# 485.net
KiCad netlist of a schematic drawn in Altium Designer
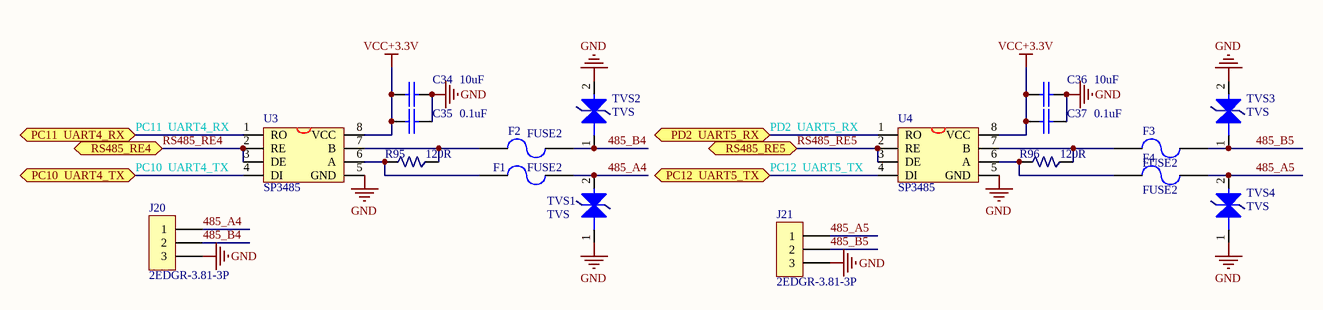
[diagram p0: 485.SchDoc]

(export (version "E")
  (design (tool "Eeschema 10.0.6"))
  (components
    (comp (ref "C34") (value "10uF") (footprint "0805") (libsource (lib "INSPUR_SCH") (part "CAP")))
    (comp (ref "C35") (value "0.1uF") (footprint "0603") (libsource (lib "INSPUR_SCH") (part "CAP")))
    (comp (ref "C36") (value "10uF") (footprint "0805") (libsource (lib "INSPUR_SCH") (part "CAP")))
    (comp (ref "C37") (value "0.1uF") (footprint "0603") (libsource (lib "INSPUR_SCH") (part "CAP")))
    (comp (ref "F1")
      (value "FUSE2")
      (footprint "0805")
      (description "SMD0805P010TS")
      (libsource (lib "INSPUR_SCH") (part "FUSE2"))
    )
    (comp (ref "F2")
      (value "FUSE2")
      (footprint "0805")
      (description "SMD0805P010TS")
      (libsource (lib "INSPUR_SCH") (part "FUSE2"))
    )
    (comp (ref "F3")
      (value "FUSE2")
      (footprint "0805")
      (description "SMD0805P010TS")
      (libsource (lib "INSPUR_SCH") (part "FUSE2"))
    )
    (comp (ref "F4")
      (value "FUSE2")
      (footprint "0805")
      (description "SMD0805P010TS")
      (libsource (lib "INSPUR_SCH") (part "FUSE2"))
    )
    (comp (ref "J20")
      (value "2EDGR-3.81-3P")
      (footprint "3.81-3P")
      (libsource (lib "INSPUR_PCB") (part "SIP3A-2.50（带槽）"))
    )
    (comp (ref "J21")
      (value "2EDGR-3.81-3P")
      (footprint "3.81-3P")
      (libsource (lib "INSPUR_PCB") (part "SIP3A-2.50（带槽）"))
    )
    (comp (ref "R95")
      (value "120R")
      (footprint "0603")
      (description "高精度电阻")
      (libsource (lib "8CF_V6") (part "RES-1%"))
    )
    (comp (ref "R96")
      (value "120R")
      (footprint "0603")
      (description "高精度电阻")
      (libsource (lib "8CF_V6") (part "RES-1%"))
    )
    (comp (ref "TVS1")
      (value "TVS")
      (footprint "SMB")
      (description "SMBJ12CA")
      (libsource (lib "INSPUR_SCH") (part "TVS"))
    )
    (comp (ref "TVS2")
      (value "TVS")
      (footprint "SMB")
      (description "SMBJ12CA")
      (libsource (lib "INSPUR_SCH") (part "TVS"))
    )
    (comp (ref "TVS3")
      (value "TVS")
      (footprint "SMB")
      (description "SMBJ12CA")
      (libsource (lib "INSPUR_SCH") (part "TVS"))
    )
    (comp (ref "TVS4")
      (value "TVS")
      (footprint "SMB")
      (description "SMBJ12CA")
      (libsource (lib "INSPUR_SCH") (part "TVS"))
    )
    (comp (ref "U3") (value "SP3485") (footprint "SOP-8") (libsource (lib "mylib") (part "MAX3485")))
    (comp (ref "U4") (value "SP3485") (footprint "SOP-8") (libsource (lib "mylib") (part "MAX3485")))
  )
  (nets
    (net (code "1") (name "/485_A4") (class "Default")
      (node (ref "F1") (pin "2") (pinfunction "2_2") (pintype "passive"))
      (node (ref "J20") (pin "1") (pinfunction "1_1") (pintype "passive"))
      (node (ref "TVS1") (pin "2") (pinfunction "K_2") (pintype "passive"))
    )
    (net (code "2") (name "/485_A5") (class "Default")
      (node (ref "F4") (pin "2") (pinfunction "2_2") (pintype "passive"))
      (node (ref "J21") (pin "1") (pinfunction "1_1") (pintype "passive"))
      (node (ref "TVS4") (pin "2") (pinfunction "K_2") (pintype "passive"))
    )
    (net (code "3") (name "/485_B4") (class "Default")
      (node (ref "F2") (pin "2") (pinfunction "2_2") (pintype "passive"))
      (node (ref "J20") (pin "2") (pinfunction "2_2") (pintype "passive"))
      (node (ref "TVS2") (pin "1") (pinfunction "A_1") (pintype "passive"))
    )
    (net (code "4") (name "/485_B5") (class "Default")
      (node (ref "F3") (pin "2") (pinfunction "2_2") (pintype "passive"))
      (node (ref "J21") (pin "2") (pinfunction "2_2") (pintype "passive"))
      (node (ref "TVS3") (pin "1") (pinfunction "A_1") (pintype "passive"))
    )
    (net (code "5") (name "/PC10  UART4_TX") (class "Default")
      (node (ref "U3") (pin "4") (pinfunction "DI_4") (pintype "passive"))
    )
    (net (code "6") (name "/PC11  UART4_RX") (class "Default")
      (node (ref "U3") (pin "1") (pinfunction "RO_1") (pintype "passive"))
    )
    (net (code "7") (name "/PC12  UART5_TX") (class "Default")
      (node (ref "U4") (pin "4") (pinfunction "DI_4") (pintype "passive"))
    )
    (net (code "8") (name "/PD2  UART5_RX") (class "Default")
      (node (ref "U4") (pin "1") (pinfunction "RO_1") (pintype "passive"))
    )
    (net (code "9") (name "/RS485_RE4") (class "Default")
      (node (ref "U3") (pin "2") (pinfunction "RE_2") (pintype "passive"))
      (node (ref "U3") (pin "3") (pinfunction "DE_3") (pintype "passive"))
    )
    (net (code "10") (name "/RS485_RE5") (class "Default")
      (node (ref "U4") (pin "2") (pinfunction "RE_2") (pintype "passive"))
      (node (ref "U4") (pin "3") (pinfunction "DE_3") (pintype "passive"))
    )
    (net (code "11") (name "GND") (class "Default")
      (node (ref "C34") (pin "2") (pinfunction "2_2") (pintype "passive"))
      (node (ref "C35") (pin "2") (pinfunction "2_2") (pintype "passive"))
      (node (ref "C36") (pin "2") (pinfunction "2_2") (pintype "passive"))
      (node (ref "C37") (pin "2") (pinfunction "2_2") (pintype "passive"))
      (node (ref "J20") (pin "3") (pinfunction "3_3") (pintype "passive"))
      (node (ref "J21") (pin "3") (pinfunction "3_3") (pintype "passive"))
      (node (ref "TVS1") (pin "1") (pinfunction "A_1") (pintype "passive"))
      (node (ref "TVS2") (pin "2") (pinfunction "K_2") (pintype "passive"))
      (node (ref "TVS3") (pin "2") (pinfunction "K_2") (pintype "passive"))
      (node (ref "TVS4") (pin "1") (pinfunction "A_1") (pintype "passive"))
      (node (ref "U3") (pin "5") (pinfunction "GND_5") (pintype "passive"))
      (node (ref "U4") (pin "5") (pinfunction "GND_5") (pintype "passive"))
    )
    (net (code "12") (name "Net-(U3-A)") (class "Default")
      (node (ref "F1") (pin "1") (pinfunction "1_1") (pintype "passive"))
      (node (ref "R95") (pin "2") (pintype "passive"))
      (node (ref "U3") (pin "6") (pinfunction "A_6") (pintype "passive"))
    )
    (net (code "13") (name "Net-(U3-B)") (class "Default")
      (node (ref "F2") (pin "1") (pinfunction "1_1") (pintype "passive"))
      (node (ref "R95") (pin "1") (pintype "passive"))
      (node (ref "U3") (pin "7") (pinfunction "B_7") (pintype "passive"))
    )
    (net (code "14") (name "Net-(U4-A)") (class "Default")
      (node (ref "F4") (pin "1") (pinfunction "1_1") (pintype "passive"))
      (node (ref "R96") (pin "2") (pintype "passive"))
      (node (ref "U4") (pin "6") (pinfunction "A_6") (pintype "passive"))
    )
    (net (code "15") (name "Net-(U4-B)") (class "Default")
      (node (ref "F3") (pin "1") (pinfunction "1_1") (pintype "passive"))
      (node (ref "R96") (pin "1") (pintype "passive"))
      (node (ref "U4") (pin "7") (pinfunction "B_7") (pintype "passive"))
    )
    (net (code "16") (name "VCC+3.3V") (class "Default")
      (node (ref "C34") (pin "1") (pinfunction "1_1") (pintype "passive"))
      (node (ref "C35") (pin "1") (pinfunction "1_1") (pintype "passive"))
      (node (ref "C36") (pin "1") (pinfunction "1_1") (pintype "passive"))
      (node (ref "C37") (pin "1") (pinfunction "1_1") (pintype "passive"))
      (node (ref "U3") (pin "8") (pinfunction "VCC_8") (pintype "passive"))
      (node (ref "U4") (pin "8") (pinfunction "VCC_8") (pintype "passive"))
    )
  )
)
